# main.net
KiCad netlist of a schematic drawn in EAGLE
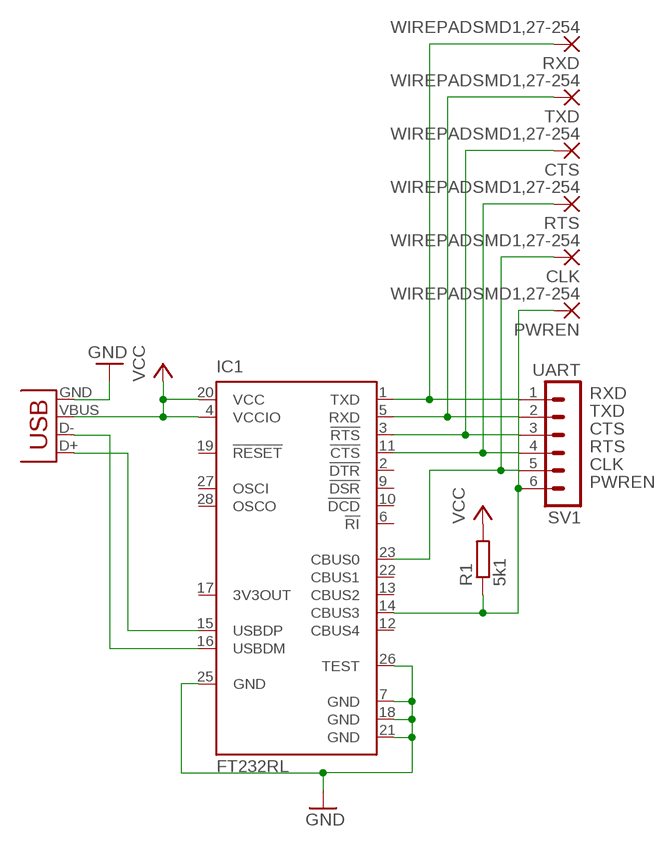
[diagram p0: schematic, sheet 1]

(export (version "E")
  (design (tool "Eeschema 10.0.6"))
  (components
    (comp (ref "CLK")
      (value "WIREPADSMD1,27-254")
      (footprint "eagle-import:SMD1,27-2,54")
      (libsource (lib "eagle-import") (part "WIREPADSMD1,27-254"))
    )
    (comp (ref "CTS")
      (value "WIREPADSMD1,27-254")
      (footprint "eagle-import:SMD1,27-2,54")
      (libsource (lib "eagle-import") (part "WIREPADSMD1,27-254"))
    )
    (comp (ref "IC1")
      (value "FT232RL")
      (footprint "eagle-import:SSOP28")
      (libsource (lib "eagle-import") (part "FT232RL"))
    )
    (comp (ref "PWREN")
      (value "WIREPADSMD1,27-254")
      (footprint "eagle-import:SMD1,27-2,54")
      (libsource (lib "eagle-import") (part "WIREPADSMD1,27-254"))
    )
    (comp (ref "R1")
      (value "5k1")
      (footprint "eagle-import:R0805")
      (libsource (lib "eagle-import") (part "R-EU_R0805"))
    )
    (comp (ref "RTS")
      (value "WIREPADSMD1,27-254")
      (footprint "eagle-import:SMD1,27-2,54")
      (libsource (lib "eagle-import") (part "WIREPADSMD1,27-254"))
    )
    (comp (ref "RXD")
      (value "WIREPADSMD1,27-254")
      (footprint "eagle-import:SMD1,27-2,54")
      (libsource (lib "eagle-import") (part "WIREPADSMD1,27-254"))
    )
    (comp (ref "SV1")
      (value "UART")
      (footprint "eagle-import:MA06-1")
      (libsource (lib "eagle-import") (part "MA06-1"))
    )
    (comp (ref "TXD")
      (value "WIREPADSMD1,27-254")
      (footprint "eagle-import:SMD1,27-2,54")
      (libsource (lib "eagle-import") (part "WIREPADSMD1,27-254"))
    )
    (comp (ref "X1")
      (value "USB-MICROB")
      (footprint "eagle-import:USB-MICROB")
      (libsource (lib "eagle-import") (part "USB-MICROB"))
    )
  )
  (nets
    (net (code "1") (name "/CLK") (class "Default")
      (node (ref "CLK") (pin "1") (pinfunction "P_1") (pintype "passive"))
      (node (ref "IC1") (pin "23") (pinfunction "CBUS0_23") (pintype "bidirectional"))
      (node (ref "SV1") (pin "5") (pinfunction "5_5") (pintype "passive"))
    )
    (net (code "2") (name "/CTS") (class "Default")
      (node (ref "CTS") (pin "1") (pinfunction "P_1") (pintype "passive"))
      (node (ref "IC1") (pin "3") (pinfunction "~{RTS}_3") (pintype "output"))
      (node (ref "SV1") (pin "3") (pinfunction "3_3") (pintype "passive"))
    )
    (net (code "3") (name "/PWREN") (class "Default")
      (node (ref "IC1") (pin "14") (pinfunction "CBUS3_14") (pintype "bidirectional"))
      (node (ref "PWREN") (pin "1") (pinfunction "P_1") (pintype "passive"))
      (node (ref "R1") (pin "1") (pinfunction "1_1") (pintype "passive"))
      (node (ref "SV1") (pin "6") (pinfunction "6_6") (pintype "passive"))
    )
    (net (code "4") (name "/RTS") (class "Default")
      (node (ref "IC1") (pin "11") (pinfunction "~{CTS}_11") (pintype "input"))
      (node (ref "RTS") (pin "1") (pinfunction "P_1") (pintype "passive"))
      (node (ref "SV1") (pin "4") (pinfunction "4_4") (pintype "passive"))
    )
    (net (code "5") (name "/RXD") (class "Default")
      (node (ref "IC1") (pin "1") (pinfunction "TXD_1") (pintype "output"))
      (node (ref "RXD") (pin "1") (pinfunction "P_1") (pintype "passive"))
      (node (ref "SV1") (pin "1") (pinfunction "1_1") (pintype "passive"))
    )
    (net (code "6") (name "/TXD") (class "Default")
      (node (ref "IC1") (pin "5") (pinfunction "RXD_5") (pintype "input"))
      (node (ref "SV1") (pin "2") (pinfunction "2_2") (pintype "passive"))
      (node (ref "TXD") (pin "1") (pinfunction "P_1") (pintype "passive"))
    )
    (net (code "7") (name "GND") (class "Default")
      (node (ref "IC1") (pin "18") (pinfunction "GND_18") (pintype "power_in"))
      (node (ref "IC1") (pin "21") (pinfunction "GND_21") (pintype "power_in"))
      (node (ref "IC1") (pin "25") (pinfunction "GND_25") (pintype "power_in"))
      (node (ref "IC1") (pin "26") (pinfunction "TEST_26") (pintype "input"))
      (node (ref "IC1") (pin "7") (pinfunction "GND_7") (pintype "power_in"))
      (node (ref "X1") (pin "GND") (pinfunction "GND_GND") (pintype "bidirectional"))
    )
    (net (code "8") (name "Net-(IC1-USBDM)") (class "Default")
      (node (ref "IC1") (pin "16") (pinfunction "USBDM_16") (pintype "bidirectional"))
      (node (ref "X1") (pin "D-") (pinfunction "D-_D-") (pintype "bidirectional"))
    )
    (net (code "9") (name "Net-(IC1-USBDP)") (class "Default")
      (node (ref "IC1") (pin "15") (pinfunction "USBDP_15") (pintype "bidirectional"))
      (node (ref "X1") (pin "D+") (pinfunction "D+_D+") (pintype "bidirectional"))
    )
    (net (code "10") (name "VCC") (class "Default")
      (node (ref "IC1") (pin "20") (pinfunction "VCC_20") (pintype "power_in"))
      (node (ref "IC1") (pin "4") (pinfunction "VCCIO_4") (pintype "power_in"))
      (node (ref "R1") (pin "2") (pinfunction "2_2") (pintype "passive"))
      (node (ref "X1") (pin "VBUS") (pinfunction "VBUS_VBUS") (pintype "bidirectional"))
    )
    (net (code "11") (name "unconnected-(IC1-3V3OUT-Pad17)") (class "Default")
      (node (ref "IC1") (pin "17") (pinfunction "3V3OUT_17") (pintype "output"))
    )
    (net (code "12") (name "unconnected-(IC1-CBUS1-Pad22)") (class "Default")
      (node (ref "IC1") (pin "22") (pinfunction "CBUS1_22") (pintype "bidirectional"))
    )
    (net (code "13") (name "unconnected-(IC1-CBUS2-Pad13)") (class "Default")
      (node (ref "IC1") (pin "13") (pinfunction "CBUS2_13") (pintype "bidirectional"))
    )
    (net (code "14") (name "unconnected-(IC1-CBUS4-Pad12)") (class "Default")
      (node (ref "IC1") (pin "12") (pinfunction "CBUS4_12") (pintype "bidirectional"))
    )
    (net (code "15") (name "unconnected-(IC1-OSCI-Pad27)") (class "Default")
      (node (ref "IC1") (pin "27") (pinfunction "OSCI_27") (pintype "input"))
    )
    (net (code "16") (name "unconnected-(IC1-OSCO-Pad28)") (class "Default")
      (node (ref "IC1") (pin "28") (pinfunction "OSCO_28") (pintype "output"))
    )
    (net (code "17") (name "unconnected-(IC1-~{DCD}-Pad10)") (class "Default")
      (node (ref "IC1") (pin "10") (pinfunction "~{DCD}_10") (pintype "input"))
    )
    (net (code "18") (name "unconnected-(IC1-~{DSR}-Pad9)") (class "Default")
      (node (ref "IC1") (pin "9") (pinfunction "~{DSR}_9") (pintype "input"))
    )
    (net (code "19") (name "unconnected-(IC1-~{DTR}-Pad2)") (class "Default")
      (node (ref "IC1") (pin "2") (pinfunction "~{DTR}_2") (pintype "output"))
    )
    (net (code "20") (name "unconnected-(IC1-~{RESET}-Pad19)") (class "Default")
      (node (ref "IC1") (pin "19") (pinfunction "~{RESET}_19") (pintype "input"))
    )
    (net (code "21") (name "unconnected-(IC1-~{RI}-Pad6)") (class "Default")
      (node (ref "IC1") (pin "6") (pinfunction "~{RI}_6") (pintype "input"))
    )
  )
)
